# pca10156_sheet8_switches.net
KiCad netlist of a schematic drawn in Altium Designer
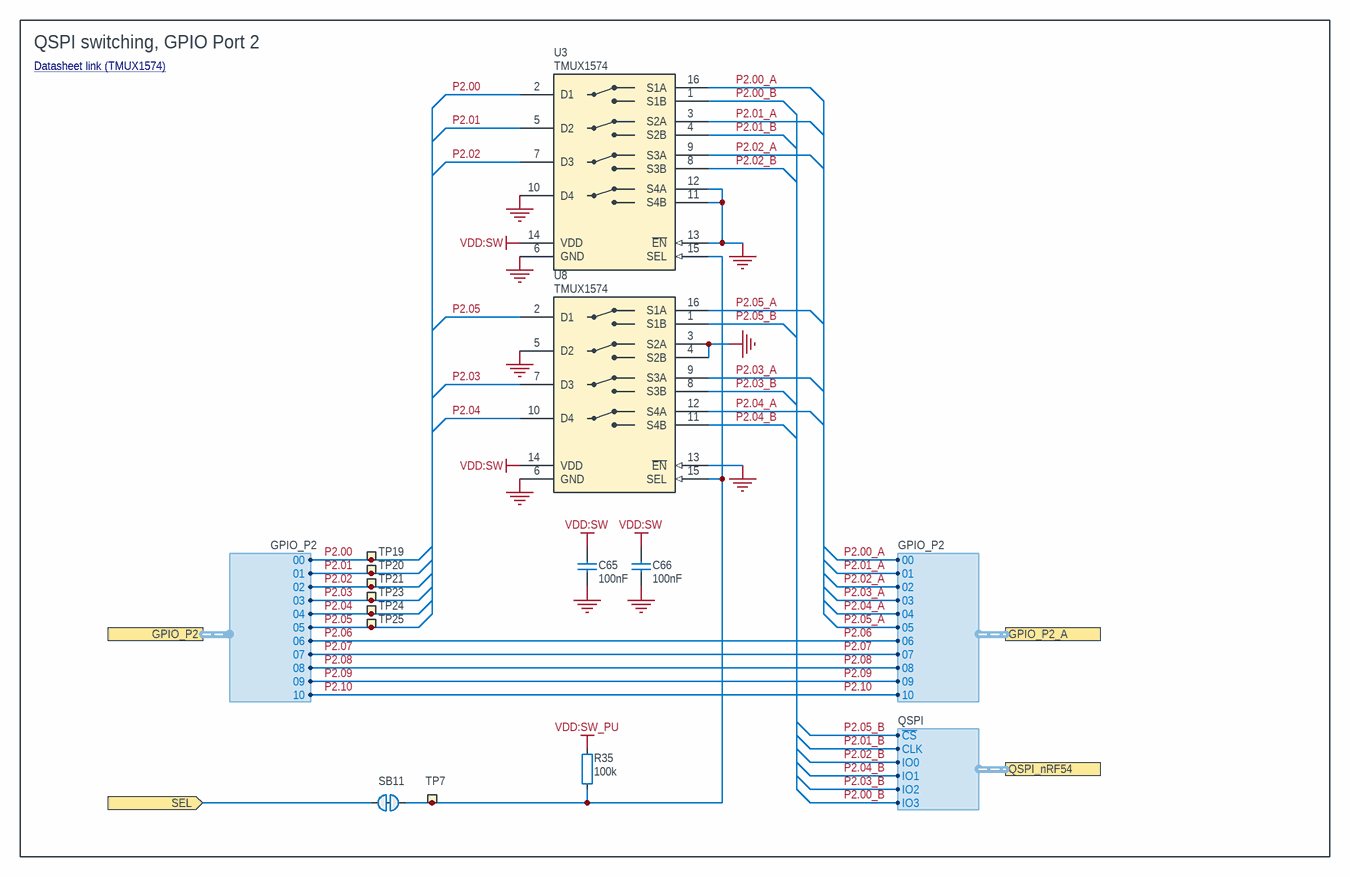
[diagram p0: pca10156_sheet8_switches.SchDoc]

(export (version "E")
  (design (tool "Eeschema 10.0.6"))
  (components
    (comp (ref "C65")
      (value "100nF")
      (footprint "CAPC0603X03L_C")
      (description "Capacitor, X5R, ±10%")
      (fields
        (field (name "PART NUMBER") "C0201-100n")
        (field (name "MANUFACTURER") "N.A.")
        (field (name "AUTHOR") "rsk")
      )
      (libsource (lib "AltiumLib") (part "CAP"))
    )
    (comp (ref "C66")
      (value "100nF")
      (footprint "CAPC0603X03L_C")
      (description "Capacitor, X5R, ±10%")
      (fields
        (field (name "PART NUMBER") "C0201-100n")
        (field (name "MANUFACTURER") "N.A.")
        (field (name "AUTHOR") "rsk")
      )
      (libsource (lib "AltiumLib") (part "CAP"))
    )
    (comp (ref "R35")
      (value "100k")
      (footprint "RESC0603X03L_C")
      (description "Resistor, ±1%, 0.05W")
      (fields
        (field (name "PART NUMBER") "R0201-100k")
        (field (name "MANUFACTURER") "N.A.")
        (field (name "AUTHOR") "rsk")
      )
      (libsource (lib "AltiumLib") (part "RES"))
    )
    (comp (ref "SB11")
      (value "Solderbridge")
      (footprint "Solderbridge_Shorted")
      (description "Shorted Solderbridge")
      (fields
        (field (name "PART NUMBER") "Solderbridge Shorted")
        (field (name "MANUFACTURER") "N.A.")
        (field (name "AUTHOR") "rsk")
      )
      (libsource (lib "AltiumLib") (part "SOLDERBRIDGE_SHORTED"))
    )
    (comp (ref "TP7")
      (value "Ø0.7mm,SMD")
      (footprint "TP_SMD_D0.7mm")
      (description "0.7mm circular SMD testpad")
      (fields
        (field (name "PART NUMBER") "TP_SMD_Ø0.7MM")
        (field (name "MANUFACTURER") "Nordic Semiconductor")
        (field (name "AUTHOR") "rsk")
      )
      (libsource (lib "AltiumLib") (part "TESTPAD"))
    )
    (comp (ref "TP19")
      (value "Ø0.7mm,SMD")
      (footprint "TP_SMD_D0.7mm")
      (description "0.7mm circular SMD testpad")
      (fields
        (field (name "PART NUMBER") "TP_SMD_Ø0.7MM")
        (field (name "MANUFACTURER") "Nordic Semiconductor")
        (field (name "AUTHOR") "rsk")
      )
      (libsource (lib "AltiumLib") (part "TESTPAD"))
    )
    (comp (ref "TP20")
      (value "Ø0.7mm,SMD")
      (footprint "TP_SMD_D0.7mm")
      (description "0.7mm circular SMD testpad")
      (fields
        (field (name "PART NUMBER") "TP_SMD_Ø0.7MM")
        (field (name "MANUFACTURER") "Nordic Semiconductor")
        (field (name "AUTHOR") "rsk")
      )
      (libsource (lib "AltiumLib") (part "TESTPAD"))
    )
    (comp (ref "TP21")
      (value "Ø0.7mm,SMD")
      (footprint "TP_SMD_D0.7mm")
      (description "0.7mm circular SMD testpad")
      (fields
        (field (name "PART NUMBER") "TP_SMD_Ø0.7MM")
        (field (name "MANUFACTURER") "Nordic Semiconductor")
        (field (name "AUTHOR") "rsk")
      )
      (libsource (lib "AltiumLib") (part "TESTPAD"))
    )
    (comp (ref "TP23")
      (value "Ø0.7mm,SMD")
      (footprint "TP_SMD_D0.7mm")
      (description "0.7mm circular SMD testpad")
      (fields
        (field (name "PART NUMBER") "TP_SMD_Ø0.7MM")
        (field (name "MANUFACTURER") "Nordic Semiconductor")
        (field (name "AUTHOR") "rsk")
      )
      (libsource (lib "AltiumLib") (part "TESTPAD"))
    )
    (comp (ref "TP24")
      (value "Ø0.7mm,SMD")
      (footprint "TP_SMD_D0.7mm")
      (description "0.7mm circular SMD testpad")
      (fields
        (field (name "PART NUMBER") "TP_SMD_Ø0.7MM")
        (field (name "MANUFACTURER") "Nordic Semiconductor")
        (field (name "AUTHOR") "rsk")
      )
      (libsource (lib "AltiumLib") (part "TESTPAD"))
    )
    (comp (ref "TP25")
      (value "Ø0.7mm,SMD")
      (footprint "TP_SMD_D0.7mm")
      (description "0.7mm circular SMD testpad")
      (fields
        (field (name "PART NUMBER") "TP_SMD_Ø0.7MM")
        (field (name "MANUFACTURER") "Nordic Semiconductor")
        (field (name "AUTHOR") "rsk")
      )
      (libsource (lib "AltiumLib") (part "TESTPAD"))
    )
    (comp (ref "U3")
      (value "TMUX1574")
      (footprint "XQFN40P180X260X50-16N")
      (description "Low-Capacitance, 2:1 (SPDT) 4-Channel, analog switch")
      (fields
        (field (name "MANUFACTURER") "Texas Instruments")
        (field (name "MANUFACTURER PART NUMBER") "TMUX1574RSVR")
        (field (name "AUTHOR") "stl1")
      )
      (libsource (lib "AltiumLib") (part "TMUX1574_RSV"))
    )
    (comp (ref "U8")
      (value "TMUX1574")
      (footprint "XQFN40P180X260X50-16N")
      (description "Low-Capacitance, 2:1 (SPDT) 4-Channel, analog switch")
      (fields
        (field (name "MANUFACTURER") "Texas Instruments")
        (field (name "MANUFACTURER PART NUMBER") "TMUX1574RSVR")
        (field (name "AUTHOR") "stl1")
      )
      (libsource (lib "AltiumLib") (part "TMUX1574_RSV"))
    )
  )
  (nets
    (net (code "3") (name "/P2.00") (class "Default")
      (node (ref "TP19") (pin "1") (pinfunction "1_1") (pintype "passive"))
      (node (ref "U3") (pin "2") (pinfunction "D1_2") (pintype "passive"))
    )
    (net (code "4") (name "/P2.00_A") (class "Default")
      (node (ref "U3") (pin "16") (pinfunction "S1A_16") (pintype "passive"))
    )
    (net (code "5") (name "/P2.00_B") (class "Default")
      (node (ref "U3") (pin "1") (pinfunction "S1B_1") (pintype "passive"))
    )
    (net (code "6") (name "/P2.01") (class "Default")
      (node (ref "TP20") (pin "1") (pinfunction "1_1") (pintype "passive"))
      (node (ref "U3") (pin "5") (pinfunction "D2_5") (pintype "passive"))
    )
    (net (code "7") (name "/P2.01_A") (class "Default")
      (node (ref "U3") (pin "3") (pinfunction "S2A_3") (pintype "passive"))
    )
    (net (code "8") (name "/P2.01_B") (class "Default")
      (node (ref "U3") (pin "4") (pinfunction "S2B_4") (pintype "passive"))
    )
    (net (code "9") (name "/P2.02") (class "Default")
      (node (ref "TP21") (pin "1") (pinfunction "1_1") (pintype "passive"))
      (node (ref "U3") (pin "7") (pinfunction "D3_7") (pintype "passive"))
    )
    (net (code "10") (name "/P2.02_A") (class "Default")
      (node (ref "U3") (pin "9") (pinfunction "S3A_9") (pintype "passive"))
    )
    (net (code "11") (name "/P2.02_B") (class "Default")
      (node (ref "U3") (pin "8") (pinfunction "S3B_8") (pintype "passive"))
    )
    (net (code "12") (name "/P2.03") (class "Default")
      (node (ref "TP23") (pin "1") (pinfunction "1_1") (pintype "passive"))
      (node (ref "U8") (pin "7") (pinfunction "D3_7") (pintype "passive"))
    )
    (net (code "13") (name "/P2.03_A") (class "Default")
      (node (ref "U8") (pin "9") (pinfunction "S3A_9") (pintype "passive"))
    )
    (net (code "14") (name "/P2.03_B") (class "Default")
      (node (ref "U8") (pin "8") (pinfunction "S3B_8") (pintype "passive"))
    )
    (net (code "15") (name "/P2.04") (class "Default")
      (node (ref "TP24") (pin "1") (pinfunction "1_1") (pintype "passive"))
      (node (ref "U8") (pin "10") (pinfunction "D4_10") (pintype "passive"))
    )
    (net (code "16") (name "/P2.04_A") (class "Default")
      (node (ref "U8") (pin "12") (pinfunction "S4A_12") (pintype "passive"))
    )
    (net (code "17") (name "/P2.04_B") (class "Default")
      (node (ref "U8") (pin "11") (pinfunction "S4B_11") (pintype "passive"))
    )
    (net (code "18") (name "/P2.05") (class "Default")
      (node (ref "TP25") (pin "1") (pinfunction "1_1") (pintype "passive"))
      (node (ref "U8") (pin "2") (pinfunction "D1_2") (pintype "passive"))
    )
    (net (code "19") (name "/P2.05_A") (class "Default")
      (node (ref "U8") (pin "16") (pinfunction "S1A_16") (pintype "passive"))
    )
    (net (code "20") (name "/P2.05_B") (class "Default")
      (node (ref "U8") (pin "1") (pinfunction "S1B_1") (pintype "passive"))
    )
    (net (code "26") (name "/SEL") (class "Default")
      (node (ref "SB11") (pin "1") (pinfunction "0_1") (pintype "passive"))
    )
    (net (code "29") (name "GND") (class "Default")
      (node (ref "C65") (pin "2") (pinfunction "2_2") (pintype "passive"))
      (node (ref "C66") (pin "2") (pinfunction "2_2") (pintype "passive"))
      (node (ref "U3") (pin "10") (pinfunction "D4_10") (pintype "passive"))
      (node (ref "U3") (pin "11") (pinfunction "S4B_11") (pintype "passive"))
      (node (ref "U3") (pin "12") (pinfunction "S4A_12") (pintype "passive"))
      (node (ref "U3") (pin "13") (pinfunction "~{EN}_13") (pintype "input"))
      (node (ref "U3") (pin "6") (pinfunction "GND_6") (pintype "power_in"))
      (node (ref "U8") (pin "13") (pinfunction "~{EN}_13") (pintype "input"))
      (node (ref "U8") (pin "3") (pinfunction "S2A_3") (pintype "passive"))
      (node (ref "U8") (pin "4") (pinfunction "S2B_4") (pintype "passive"))
      (node (ref "U8") (pin "5") (pinfunction "D2_5") (pintype "passive"))
      (node (ref "U8") (pin "6") (pinfunction "GND_6") (pintype "power_in"))
    )
    (net (code "30") (name "Net-(SB11-1)") (class "Default")
      (node (ref "R35") (pin "1") (pinfunction "1_1") (pintype "passive"))
      (node (ref "SB11") (pin "2") (pinfunction "1_2") (pintype "passive"))
      (node (ref "TP7") (pin "1") (pinfunction "1_1") (pintype "passive"))
      (node (ref "U3") (pin "15") (pinfunction "SEL_15") (pintype "input"))
      (node (ref "U8") (pin "15") (pinfunction "SEL_15") (pintype "input"))
    )
    (net (code "31") (name "VDD:SW") (class "Default")
      (node (ref "C65") (pin "1") (pinfunction "1_1") (pintype "passive"))
      (node (ref "C66") (pin "1") (pinfunction "1_1") (pintype "passive"))
      (node (ref "U3") (pin "14") (pinfunction "VDD_14") (pintype "power_in"))
      (node (ref "U8") (pin "14") (pinfunction "VDD_14") (pintype "power_in"))
    )
    (net (code "32") (name "VDD:SW_PU") (class "Default")
      (node (ref "R35") (pin "2") (pinfunction "2_2") (pintype "passive"))
    )
  )
)
